# USB_INTERFACES.net
KiCad netlist of a schematic drawn in Altium Designer
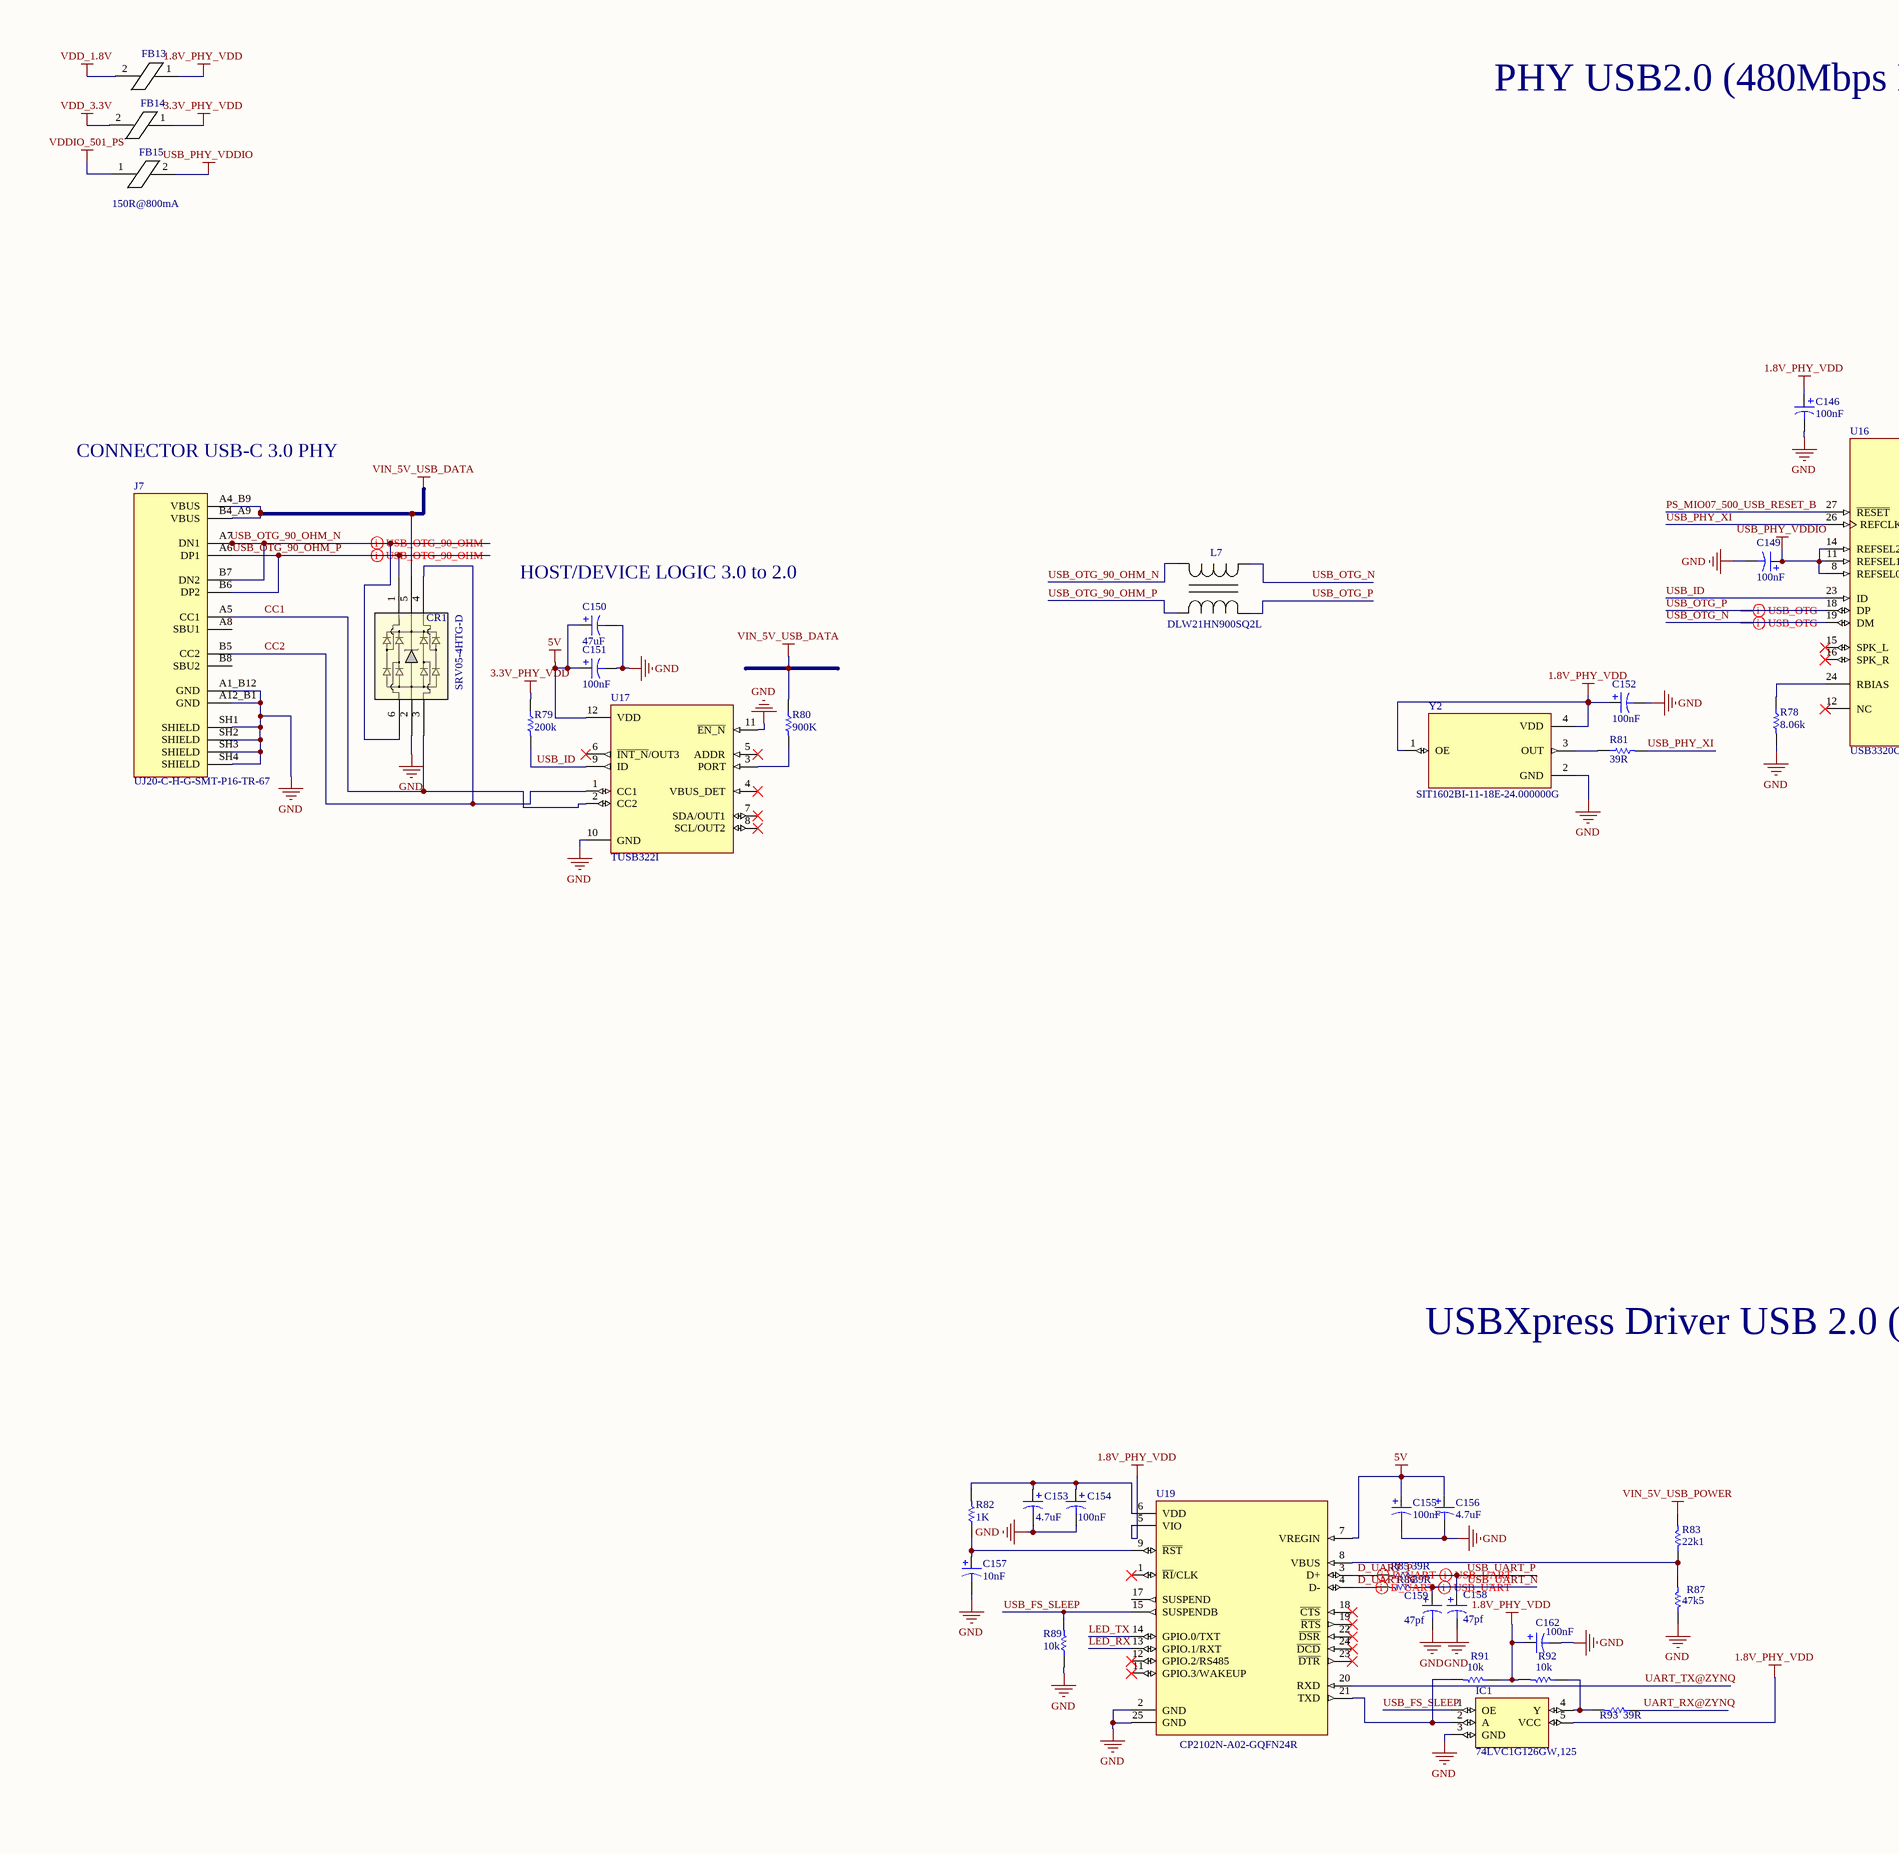
[diagram p0: USB INTERFACES.SchDoc, left]
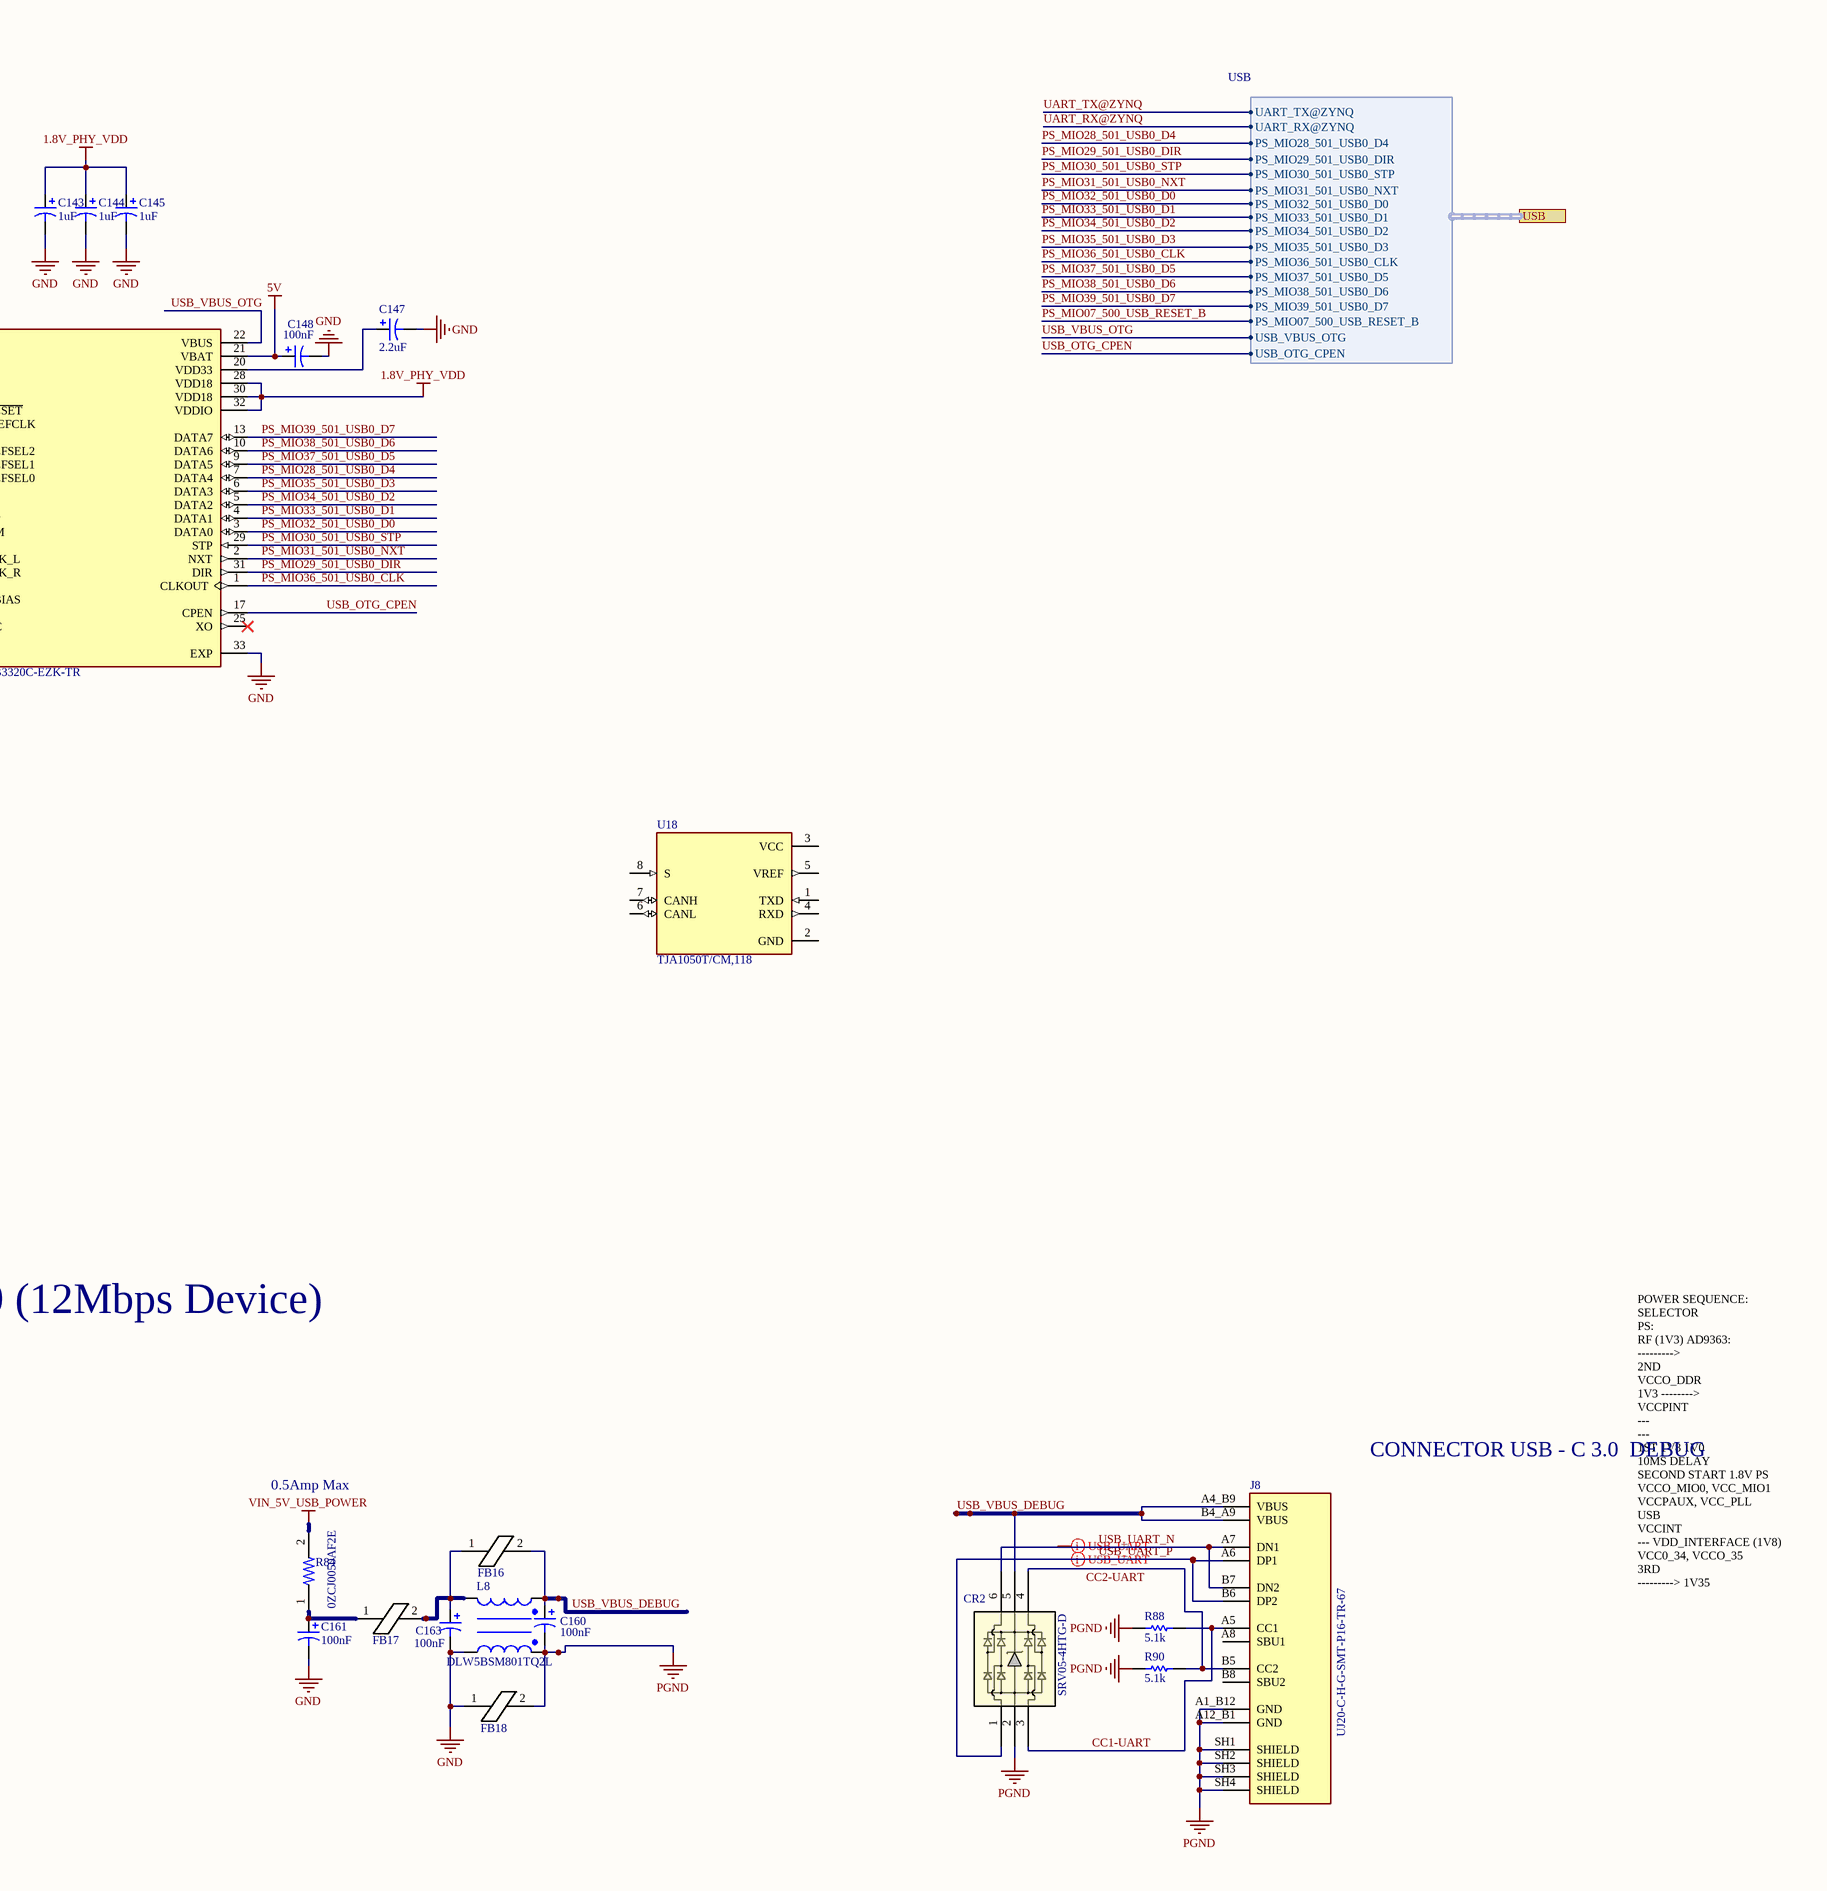
[diagram p1: USB INTERFACES.SchDoc, right]

(export (version "E")
  (design (tool "Eeschema 10.0.6"))
  (components
    (comp (ref "C143")
      (value "1uF")
      (footprint "C0805")
      (description "Polarized Capacitor (Surface Mount)")
      (fields (field (name "Comment") "Cap Pol3") (field (name "PUBLISHER") "Altium Limited"))
      (libsource (lib "") (part "Cap Pol3_1"))
    )
    (comp (ref "C144")
      (value "1uF")
      (footprint "C0805")
      (description "Polarized Capacitor (Surface Mount)")
      (fields (field (name "Comment") "Cap Pol3") (field (name "PUBLISHER") "Altium Limited"))
      (libsource (lib "") (part "Cap Pol3_1"))
    )
    (comp (ref "C145")
      (value "1uF")
      (footprint "C0805")
      (description "Polarized Capacitor (Surface Mount)")
      (fields (field (name "Comment") "Cap Pol3") (field (name "PUBLISHER") "Altium Limited"))
      (libsource (lib "") (part "Cap Pol3_1"))
    )
    (comp (ref "C146")
      (value "100nF")
      (footprint "C0805")
      (description "Polarized Capacitor (Surface Mount)")
      (fields (field (name "Comment") "Cap Pol3") (field (name "PUBLISHER") "Altium Limited"))
      (libsource (lib "") (part "Cap Pol3_1"))
    )
    (comp (ref "C147")
      (value "2.2uF")
      (footprint "C0805")
      (description "Polarized Capacitor (Surface Mount)")
      (fields (field (name "Comment") "Cap Pol3") (field (name "PUBLISHER") "Altium Limited"))
      (libsource (lib "") (part "Cap Pol3_1"))
    )
    (comp (ref "C148")
      (value "100nF")
      (footprint "C0805")
      (description "Polarized Capacitor (Surface Mount)")
      (fields (field (name "Comment") "Cap Pol3") (field (name "PUBLISHER") "Altium Limited"))
      (libsource (lib "") (part "Cap Pol3_1"))
    )
    (comp (ref "C149")
      (value "100nF")
      (footprint "C0805")
      (description "Polarized Capacitor (Surface Mount)")
      (fields (field (name "Comment") "Cap Pol3") (field (name "PUBLISHER") "Altium Limited"))
      (libsource (lib "") (part "Cap Pol3_1"))
    )
    (comp (ref "C150")
      (value "47uF")
      (footprint "C0805")
      (description "Polarized Capacitor (Surface Mount)")
      (fields (field (name "Comment") "Cap Pol3") (field (name "PUBLISHER") "Altium Limited"))
      (libsource (lib "") (part "Cap Pol3_1"))
    )
    (comp (ref "C151")
      (value "100nF")
      (footprint "C0805")
      (description "Polarized Capacitor (Surface Mount)")
      (fields (field (name "Comment") "Cap Pol3") (field (name "PUBLISHER") "Altium Limited"))
      (libsource (lib "") (part "Cap Pol3_1"))
    )
    (comp (ref "C152")
      (value "100nF")
      (footprint "C0805")
      (description "Polarized Capacitor (Surface Mount)")
      (fields (field (name "Comment") "Cap Pol3") (field (name "PUBLISHER") "Altium Limited"))
      (libsource (lib "") (part "Cap Pol3_1"))
    )
    (comp (ref "C153")
      (value "4.7uF")
      (footprint "C0805")
      (description "Polarized Capacitor (Surface Mount)")
      (fields (field (name "Comment") "Cap Pol3") (field (name "PUBLISHER") "Altium Limited"))
      (libsource (lib "") (part "Cap Pol3_1"))
    )
    (comp (ref "C154")
      (value "100nF")
      (footprint "C0805")
      (description "Polarized Capacitor (Surface Mount)")
      (fields (field (name "Comment") "Cap Pol3") (field (name "PUBLISHER") "Altium Limited"))
      (libsource (lib "") (part "Cap Pol3_1"))
    )
    (comp (ref "C155")
      (value "100nF")
      (footprint "C0805")
      (description "Polarized Capacitor (Surface Mount)")
      (fields (field (name "Comment") "Cap Pol3") (field (name "PUBLISHER") "Altium Limited"))
      (libsource (lib "Miscellaneous Devices") (part "Cap Pol3"))
    )
    (comp (ref "C156")
      (value "4.7uF")
      (footprint "C0805")
      (description "Polarized Capacitor (Surface Mount)")
      (fields (field (name "Comment") "Cap Pol3") (field (name "PUBLISHER") "Altium Limited"))
      (libsource (lib "Miscellaneous Devices") (part "Cap Pol3"))
    )
    (comp (ref "C157")
      (value "10nF")
      (footprint "C0805")
      (description "Polarized Capacitor (Surface Mount)")
      (fields (field (name "Comment") "Cap Pol3") (field (name "PUBLISHER") "Altium Limited"))
      (libsource (lib "Miscellaneous Devices") (part "Cap Pol3"))
    )
    (comp (ref "C158")
      (value "47pf")
      (footprint "C0805")
      (description "Polarized Capacitor (Surface Mount)")
      (fields (field (name "Comment") "Cap Pol3") (field (name "PUBLISHER") "Altium Limited"))
      (libsource (lib "Miscellaneous Devices") (part "Cap Pol3"))
    )
    (comp (ref "C159")
      (value "47pf")
      (footprint "C0805")
      (description "Polarized Capacitor (Surface Mount)")
      (fields (field (name "Comment") "Cap Pol3") (field (name "PUBLISHER") "Altium Limited"))
      (libsource (lib "Miscellaneous Devices") (part "Cap Pol3"))
    )
    (comp (ref "C160")
      (value "100nF")
      (footprint "C0805")
      (description "Polarized Capacitor (Surface Mount)")
      (fields (field (name "Comment") "Cap Pol3") (field (name "PUBLISHER") "Altium Limited"))
      (libsource (lib "") (part "Cap Pol3_1"))
    )
    (comp (ref "C161")
      (value "100nF")
      (footprint "C0805")
      (description "Polarized Capacitor (Surface Mount)")
      (fields (field (name "Comment") "Cap Pol3") (field (name "PUBLISHER") "Altium Limited"))
      (libsource (lib "") (part "Cap Pol3_1"))
    )
    (comp (ref "C162")
      (value "100nF")
      (footprint "C0805")
      (description "Polarized Capacitor (Surface Mount)")
      (fields (field (name "Comment") "Cap Pol3") (field (name "PUBLISHER") "Altium Limited"))
      (libsource (lib "") (part "Cap Pol3_1"))
    )
    (comp (ref "C163")
      (value "100nF")
      (footprint "C0805")
      (description "Polarized Capacitor (Surface Mount)")
      (fields (field (name "Comment") "Cap Pol3") (field (name "PUBLISHER") "Altium Limited"))
      (libsource (lib "") (part "Cap Pol3_1"))
    )
    (comp (ref "CR1")
      (value "SRV05-4HTG-D")
      (footprint "SOIC6_SOT23-6_CRA_LTF")
      (description "No Description Available")
      (libsource (lib "SRV05-4HTG-D") (part "SRV05-4HTG-D"))
    )
    (comp (ref "CR2")
      (value "SRV05-4HTG-D")
      (footprint "SOIC6_SOT23-6_CRA_LTF")
      (description "No Description Available")
      (libsource (lib "") (part "SRV05-4HTG-D_1"))
    )
    (comp (ref "FB13")
      (value "FERRITA")
      (footprint "0805R")
      (libsource (lib "lib_protel_HC") (part "FERRITA"))
    )
    (comp (ref "FB14")
      (value "FERRITA")
      (footprint "0805R")
      (libsource (lib "lib_protel_HC") (part "FERRITA"))
    )
    (comp (ref "FB15")
      (value "FERRITA")
      (footprint "0805R")
      (libsource (lib "lib_protel_HC") (part "FERRITA"))
    )
    (comp (ref "FB16")
      (value "FERRITA")
      (footprint "0805R")
      (libsource (lib "lib_protel_HC") (part "FERRITA"))
    )
    (comp (ref "FB17")
      (value "FERRITA")
      (footprint "0805R")
      (libsource (lib "lib_protel_HC") (part "FERRITA"))
    )
    (comp (ref "FB18")
      (value "FERRITA")
      (footprint "0805R")
      (libsource (lib "lib_protel_HC") (part "FERRITA"))
    )
    (comp (ref "IC1")
      (value "74LVC1G126GW,125")
      (footprint "SOT65P212X110-5N")
      (description "Buffer, Non-Inverting 1 Element 1 Bit per Element 3-State Output 5-TSSOP")
      (fields (field (name "MF") "Nexperia USA Inc."))
      (libsource (lib "74LVC1G126GW_125") (part "74LVC1G126GW,125"))
    )
    (comp (ref "J7")
      (value "UJ20-C-H-G-SMT-P16-TR-67")
      (footprint "SAMESKY_UJ20-C-H-G-SMT-P16-TR-67")
      (libsource (lib "") (part "UJ20-C-H-G-SMT-P16-TR-67_1"))
    )
    (comp (ref "J8")
      (value "UJ20-C-H-G-SMT-P16-TR-67")
      (footprint "SAMESKY_UJ20-C-H-G-SMT-P16-TR-67")
      (libsource (lib "UJ20-C-H-G-SMT-P16-TR-67") (part "UJ20-C-H-G-SMT-P16-TR-67"))
    )
    (comp (ref "L7")
      (value "DLW21HN900SQ2L")
      (footprint "IND_DLW21H_0805_MUR")
      (description "No Description Available")
      (libsource (lib "DLW21HN900SQ2L") (part "DLW21HN900SQ2L"))
    )
    (comp (ref "L8")
      (value "DLW5BSM801TQ2L")
      (footprint "FIL_DLW5BSM801TQ2L")
      (description "2 Line Common Mode Choke Surface Mount 800 Ohms @ 100MHz 2A DCR 56mOhm")
      (fields (field (name "MF") "Murata") (field (name "DIGI-KEY_PART_NUMBER") "490-9569-1-ND"))
      (libsource (lib "DLW5BSM801TQ2L") (part "DLW5BSM801TQ2L"))
    )
    (comp (ref "R78")
      (value "8.06k")
      (footprint "0603")
      (description "Resistor")
      (fields
        (field (name "MANUFACTURER") "Generic Components")
        (field (name "Comment") "Res1")
        (field (name "PUBLISHER") "Altium Limited")
      )
      (libsource (lib "lib_protel_HC") (part "Res1_1"))
    )
    (comp (ref "R79")
      (value "200k")
      (footprint "0603")
      (description "Resistor")
      (fields
        (field (name "MANUFACTURER") "Generic Components")
        (field (name "Comment") "Res1")
        (field (name "PUBLISHER") "Altium Limited")
      )
      (libsource (lib "lib_protel_HC") (part "Res1_1"))
    )
    (comp (ref "R80")
      (value "900K")
      (footprint "0603")
      (description "Resistor")
      (fields
        (field (name "MANUFACTURER") "Generic Components")
        (field (name "Comment") "Res1")
        (field (name "PUBLISHER") "Altium Limited")
      )
      (libsource (lib "lib_protel_HC") (part "Res1_1"))
    )
    (comp (ref "R81")
      (value "39R")
      (footprint "0603")
      (description "Resistor")
      (fields
        (field (name "MANUFACTURER") "Generic Components")
        (field (name "Comment") "Res1")
        (field (name "PUBLISHER") "Altium Limited")
      )
      (libsource (lib "lib_protel_HC") (part "Res1_1"))
    )
    (comp (ref "R82")
      (value "1K")
      (footprint "0603")
      (description "Resistor")
      (fields
        (field (name "MANUFACTURER") "Generic Components")
        (field (name "Comment") "Res1")
        (field (name "PUBLISHER") "Altium Limited")
      )
      (libsource (lib "lib_protel_HC") (part "Res1_1"))
    )
    (comp (ref "R83")
      (value "22k1")
      (footprint "0603")
      (description "Resistor")
      (fields
        (field (name "MANUFACTURER") "Generic Components")
        (field (name "Comment") "Res1")
        (field (name "PUBLISHER") "Altium Limited")
      )
      (libsource (lib "lib_protel_HC") (part "Res1_1"))
    )
    (comp (ref "R84")
      (value "0ZCJ0050AF2E")
      (footprint "RESC3216X125N")
      (description "1206 SMT PPTC ¦ 0.50 Ih ¦ 24V")
      (fields (field (name "MF") "Bel Fuse"))
      (libsource (lib "0ZCJ0050AF2E") (part "0ZCJ0050AF2E"))
    )
    (comp (ref "R85")
      (value "39R")
      (footprint "0603")
      (description "Resistor")
      (fields
        (field (name "MANUFACTURER") "Generic Components")
        (field (name "Comment") "Res1")
        (field (name "PUBLISHER") "Altium Limited")
      )
      (libsource (lib "lib_protel_HC") (part "Res1_1"))
    )
    (comp (ref "R86")
      (value "39R")
      (footprint "0603")
      (description "Resistor")
      (fields
        (field (name "MANUFACTURER") "Generic Components")
        (field (name "Comment") "Res1")
        (field (name "PUBLISHER") "Altium Limited")
      )
      (libsource (lib "lib_protel_HC") (part "Res1_1"))
    )
    (comp (ref "R87")
      (value "47k5")
      (footprint "0603")
      (description "Resistor")
      (fields
        (field (name "MANUFACTURER") "Generic Components")
        (field (name "Comment") "Res1")
        (field (name "PUBLISHER") "Altium Limited")
      )
      (libsource (lib "lib_protel_HC") (part "Res1_1"))
    )
    (comp (ref "R88")
      (value "5.1k")
      (footprint "0603")
      (description "Resistor")
      (fields
        (field (name "MANUFACTURER") "Generic Components")
        (field (name "Comment") "Res1")
        (field (name "PUBLISHER") "Altium Limited")
      )
      (libsource (lib "lib_protel_HC") (part "Res1_1"))
    )
    (comp (ref "R89")
      (value "10k")
      (footprint "0603")
      (description "Resistor")
      (fields
        (field (name "MANUFACTURER") "Generic Components")
        (field (name "Comment") "Res1")
        (field (name "PUBLISHER") "Altium Limited")
      )
      (libsource (lib "lib_protel_HC") (part "Res1_1"))
    )
    (comp (ref "R90")
      (value "5.1k")
      (footprint "0603")
      (description "Resistor")
      (fields
        (field (name "MANUFACTURER") "Generic Components")
        (field (name "Comment") "Res1")
        (field (name "PUBLISHER") "Altium Limited")
      )
      (libsource (lib "lib_protel_HC") (part "Res1_1"))
    )
    (comp (ref "R91")
      (value "10k")
      (footprint "0603")
      (description "Resistor")
      (fields
        (field (name "MANUFACTURER") "Generic Components")
        (field (name "Comment") "Res1")
        (field (name "PUBLISHER") "Altium Limited")
      )
      (libsource (lib "lib_protel_HC") (part "Res1_1"))
    )
    (comp (ref "R92")
      (value "10k")
      (footprint "0603")
      (description "Resistor")
      (fields
        (field (name "MANUFACTURER") "Generic Components")
        (field (name "Comment") "Res1")
        (field (name "PUBLISHER") "Altium Limited")
      )
      (libsource (lib "lib_protel_HC") (part "Res1_1"))
    )
    (comp (ref "R93")
      (value "39R")
      (footprint "0603")
      (description "Resistor")
      (fields
        (field (name "MANUFACTURER") "Generic Components")
        (field (name "Comment") "Res1")
        (field (name "PUBLISHER") "Altium Limited")
      )
      (libsource (lib "lib_protel_HC") (part "Res1_1"))
    )
    (comp (ref "U16")
      (value "USB3320C-EZK-TR")
      (footprint "QFN50P500X500X100-33N")
      (fields (field (name "MF") "Microchip"))
      (libsource (lib "USB3320C-EZK-TR") (part "USB3320C-EZK-TR"))
    )
    (comp (ref "U17")
      (value "TUSB322I")
      (footprint "IC_TUSB320IRWBR")
      (description "USB Type-C configuration channel logic and port control")
      (fields (field (name "MF") "Texas Instruments") (field (name "MP") "TUSB320IRWBR"))
      (libsource (lib "TUSB320IRWBR") (part "TUSB320IRWBR"))
    )
    (comp (ref "U18")
      (value "TJA1050T/CM,118")
      (footprint "SOIC127P600X175-8N")
      (description "1/1 Transceiver Half CANbus 8-SO")
      (fields (field (name "MF") "NXP USA"))
      (libsource (lib "TJA1050T_CM_118") (part "TJA1050T/CM,118"))
    )
    (comp (ref "U19")
      (value "CP2102N-A02-GQFN24R")
      (footprint "QFN50P400X400X80-25N")
      (libsource (lib "CP2102N-A02-GQFN24R") (part "CP2102N-A02-GQFN24R"))
    )
    (comp (ref "Y2")
      (value "SIT1602BI-11-18E-24.000000G")
      (footprint "OSC_SIT1602BI-11-18E-24.000000G")
      (description "Oscillator MEMS 24MHz Â±20ppm (Stability) 15pF HCMOS/LVCMOS 55% 1.8V 4-Pin PQFN SMD T/R")
      (fields (field (name "MF") "SiTime"))
      (libsource (lib "SIT1602BI-11-18E-24.000000G") (part "SIT1602BI-11-18E-24.000000G"))
    )
  )
  (nets
    (net (code "2") (name "/CC1") (class "Default")
      (node (ref "CR1") (pin "3") (pinfunction "3_3") (pintype "passive"))
      (node (ref "J7") (pin "A5") (pinfunction "CC1_A5") (pintype "passive"))
      (node (ref "U17") (pin "2") (pinfunction "CC2_2") (pintype "bidirectional"))
    )
    (net (code "3") (name "/CC1-UART") (class "Default")
      (node (ref "CR2") (pin "3") (pinfunction "3_3") (pintype "passive"))
      (node (ref "J8") (pin "A5") (pinfunction "CC1_A5") (pintype "passive"))
      (node (ref "R88") (pin "2") (pinfunction "2_2") (pintype "passive"))
    )
    (net (code "4") (name "/CC2") (class "Default")
      (node (ref "CR1") (pin "4") (pinfunction "4_4") (pintype "passive"))
      (node (ref "J7") (pin "B5") (pinfunction "CC2_B5") (pintype "passive"))
      (node (ref "U17") (pin "1") (pinfunction "CC1_1") (pintype "bidirectional"))
    )
    (net (code "5") (name "/CC2-UART") (class "Default")
      (node (ref "CR2") (pin "4") (pinfunction "4_4") (pintype "passive"))
      (node (ref "J8") (pin "B5") (pinfunction "CC2_B5") (pintype "passive"))
      (node (ref "R90") (pin "2") (pinfunction "2_2") (pintype "passive"))
    )
    (net (code "6") (name "/D_UART_N") (class "Default")
      (node (ref "R86") (pin "2") (pinfunction "2_2") (pintype "passive"))
      (node (ref "U19") (pin "4") (pinfunction "D-_4") (pintype "bidirectional"))
    )
    (net (code "7") (name "/D_UART_P") (class "Default")
      (node (ref "R85") (pin "2") (pinfunction "2_2") (pintype "passive"))
      (node (ref "U19") (pin "3") (pinfunction "D+_3") (pintype "bidirectional"))
    )
    (net (code "8") (name "/LED_RX") (class "Default")
      (node (ref "U19") (pin "13") (pinfunction "GPIO.1/RXT_13") (pintype "bidirectional"))
    )
    (net (code "9") (name "/LED_TX") (class "Default")
      (node (ref "U19") (pin "14") (pinfunction "GPIO.0/TXT_14") (pintype "bidirectional"))
    )
    (net (code "10") (name "/PS_MIO07_500_USB_RESET_B") (class "Default")
      (node (ref "U16") (pin "27") (pinfunction "~{RESET}_27") (pintype "input"))
    )
    (net (code "11") (name "/PS_MIO28_501_USB0_D4") (class "Default")
      (node (ref "U16") (pin "7") (pinfunction "DATA4_7") (pintype "bidirectional"))
    )
    (net (code "12") (name "/PS_MIO29_501_USB0_DIR") (class "Default")
      (node (ref "U16") (pin "31") (pinfunction "DIR_31") (pintype "output"))
    )
    (net (code "13") (name "/PS_MIO30_501_USB0_STP") (class "Default")
      (node (ref "U16") (pin "29") (pinfunction "STP_29") (pintype "input"))
    )
    (net (code "14") (name "/PS_MIO31_501_USB0_NXT") (class "Default")
      (node (ref "U16") (pin "2") (pinfunction "NXT_2") (pintype "output"))
    )
    (net (code "15") (name "/PS_MIO32_501_USB0_D0") (class "Default")
      (node (ref "U16") (pin "3") (pinfunction "DATA0_3") (pintype "bidirectional"))
    )
    (net (code "16") (name "/PS_MIO33_501_USB0_D1") (class "Default")
      (node (ref "U16") (pin "4") (pinfunction "DATA1_4") (pintype "bidirectional"))
    )
    (net (code "17") (name "/PS_MIO34_501_USB0_D2") (class "Default")
      (node (ref "U16") (pin "5") (pinfunction "DATA2_5") (pintype "bidirectional"))
    )
    (net (code "18") (name "/PS_MIO35_501_USB0_D3") (class "Default")
      (node (ref "U16") (pin "6") (pinfunction "DATA3_6") (pintype "bidirectional"))
    )
    (net (code "19") (name "/PS_MIO36_501_USB0_CLK") (class "Default")
      (node (ref "U16") (pin "1") (pinfunction "CLKOUT_1") (pintype "output"))
    )
    (net (code "20") (name "/PS_MIO37_501_USB0_D5") (class "Default")
      (node (ref "U16") (pin "9") (pinfunction "DATA5_9") (pintype "bidirectional"))
    )
    (net (code "21") (name "/PS_MIO38_501_USB0_D6") (class "Default")
      (node (ref "U16") (pin "10") (pinfunction "DATA6_10") (pintype "bidirectional"))
    )
    (net (code "22") (name "/PS_MIO39_501_USB0_D7") (class "Default")
      (node (ref "U16") (pin "13") (pinfunction "DATA7_13") (pintype "bidirectional"))
    )
    (net (code "23") (name "/UART_RX@ZYNQ") (class "Default")
      (node (ref "R93") (pin "1") (pinfunction "1_1") (pintype "passive"))
    )
    (net (code "24") (name "/UART_TX@ZYNQ") (class "Default")
      (node (ref "U19") (pin "20") (pinfunction "RXD_20") (pintype "input"))
    )
    (net (code "25") (name "/USB_FS_SLEEP") (class "Default")
      (node (ref "IC1") (pin "1") (pinfunction "OE_1") (pintype "bidirectional"))
      (node (ref "R89") (pin "2") (pinfunction "2_2") (pintype "passive"))
      (node (ref "U19") (pin "15") (pinfunction "SUSPENDB_15") (pintype "output"))
    )
    (net (code "26") (name "/USB_ID") (class "Default")
      (node (ref "R79") (pin "2") (pinfunction "2_2") (pintype "passive"))
      (node (ref "U16") (pin "23") (pinfunction "ID_23") (pintype "input"))
      (node (ref "U17") (pin "9") (pinfunction "ID_9") (pintype "output"))
    )
    (net (code "27") (name "/USB_OTG_90_OHM_N") (class "Default")
      (node (ref "CR1") (pin "6") (pinfunction "6_6") (pintype "passive"))
      (node (ref "J7") (pin "A7") (pinfunction "DN1_A7") (pintype "passive"))
      (node (ref "J7") (pin "B7") (pinfunction "DN2_B7") (pintype "passive"))
      (node (ref "L7") (pin "1") (pinfunction "1_1") (pintype "passive"))
    )
    (net (code "28") (name "/USB_OTG_90_OHM_P") (class "Default")
      (node (ref "CR1") (pin "1") (pinfunction "1_1") (pintype "passive"))
      (node (ref "J7") (pin "A6") (pinfunction "DP1_A6") (pintype "passive"))
      (node (ref "J7") (pin "B6") (pinfunction "DP2_B6") (pintype "passive"))
      (node (ref "L7") (pin "4") (pinfunction "4_4") (pintype "passive"))
    )
    (net (code "29") (name "/USB_OTG_CPEN") (class "Default")
      (node (ref "U16") (pin "17") (pinfunction "CPEN_17") (pintype "output"))
    )
    (net (code "30") (name "/USB_OTG_N") (class "Default")
      (node (ref "L7") (pin "2") (pinfunction "2_2") (pintype "passive"))
      (node (ref "U16") (pin "19") (pinfunction "DM_19") (pintype "bidirectional"))
    )
    (net (code "31") (name "/USB_OTG_P") (class "Default")
      (node (ref "L7") (pin "3") (pinfunction "3_3") (pintype "passive"))
      (node (ref "U16") (pin "18") (pinfunction "DP_18") (pintype "bidirectional"))
    )
    (net (code "32") (name "/USB_PHY_XI") (class "Default")
      (node (ref "R81") (pin "2") (pinfunction "2_2") (pintype "passive"))
      (node (ref "U16") (pin "26") (pinfunction "REFCLK_26") (pintype "input"))
    )
    (net (code "33") (name "/USB_UART_N") (class "Default")
      (node (ref "C159") (pin "1") (pinfunction "1_1") (pintype "passive"))
      (node (ref "CR2") (pin "6") (pinfunction "6_6") (pintype "passive"))
      (node (ref "J8") (pin "A7") (pinfunction "DN1_A7") (pintype "passive"))
      (node (ref "J8") (pin "B7") (pinfunction "DN2_B7") (pintype "passive"))
      (node (ref "R86") (pin "1") (pinfunction "1_1") (pintype "passive"))
    )
    (net (code "34") (name "/USB_UART_P") (class "Default")
      (node (ref "C158") (pin "1") (pinfunction "1_1") (pintype "passive"))
      (node (ref "CR2") (pin "1") (pinfunction "1_1") (pintype "passive"))
      (node (ref "J8") (pin "A6") (pinfunction "DP1_A6") (pintype "passive"))
      (node (ref "J8") (pin "B6") (pinfunction "DP2_B6") (pintype "passive"))
      (node (ref "R85") (pin "1") (pinfunction "1_1") (pintype "passive"))
    )
    (net (code "35") (name "/USB_VBUS_DEBUG") (class "Default")
      (node (ref "C160") (pin "1") (pinfunction "1_1") (pintype "passive"))
      (node (ref "CR2") (pin "5") (pinfunction "5_5") (pintype "passive"))
      (node (ref "FB16") (pin "2") (pintype "passive"))
      (node (ref "J8") (pin "A4_B9") (pinfunction "VBUS_A4_B9") (pintype "passive"))
      (node (ref "J8") (pin "B4_A9") (pinfunction "VBUS_B4_A9") (pintype "passive"))
      (node (ref "L8") (pin "1") (pinfunction "1_1") (pintype "passive"))
    )
    (net (code "36") (name "/USB_VBUS_OTG") (class "Default")
      (node (ref "U16") (pin "22") (pinfunction "VBUS_22") (pintype "power_in"))
    )
    (net (code "38") (name "1.8V_PHY_VDD") (class "Default")
      (node (ref "C143") (pin "1") (pinfunction "1_1") (pintype "passive"))
      (node (ref "C144") (pin "1") (pinfunction "1_1") (pintype "passive"))
      (node (ref "C145") (pin "1") (pinfunction "1_1") (pintype "passive"))
      (node (ref "C146") (pin "1") (pinfunction "1_1") (pintype "passive"))
      (node (ref "C152") (pin "1") (pinfunction "1_1") (pintype "passive"))
      (node (ref "C162") (pin "1") (pinfunction "1_1") (pintype "passive"))
      (node (ref "FB13") (pin "1") (pintype "passive"))
      (node (ref "IC1") (pin "5") (pinfunction "VCC_5") (pintype "bidirectional"))
      (node (ref "R91") (pin "1") (pinfunction "1_1") (pintype "passive"))
      (node (ref "R92") (pin "2") (pinfunction "2_2") (pintype "passive"))
      (node (ref "U16") (pin "28") (pinfunction "VDD18_28") (pintype "power_in"))
      (node (ref "U16") (pin "30") (pinfunction "VDD18_30") (pintype "power_in"))
      (node (ref "U16") (pin "32") (pinfunction "VDDIO_32") (pintype "power_in"))
      (node (ref "U19") (pin "5") (pinfunction "VIO_5") (pintype "power_in"))
      (node (ref "Y2") (pin "1") (pinfunction "OE_1") (pintype "bidirectional"))
      (node (ref "Y2") (pin "4") (pinfunction "VDD_4") (pintype "power_in"))
    )
    (net (code "39") (name "3.3V_PHY_VDD") (class "Default")
      (node (ref "FB14") (pin "1") (pintype "passive"))
      (node (ref "R79") (pin "1") (pinfunction "1_1") (pintype "passive"))
    )
    (net (code "40") (name "5V") (class "Default")
      (node (ref "C148") (pin "1") (pinfunction "1_1") (pintype "passive"))
      (node (ref "C150") (pin "1") (pinfunction "1_1") (pintype "passive"))
      (node (ref "C151") (pin "1") (pinfunction "1_1") (pintype "passive"))
      (node (ref "C155") (pin "1") (pinfunction "1_1") (pintype "passive"))
      (node (ref "C156") (pin "1") (pinfunction "1_1") (pintype "passive"))
      (node (ref "U16") (pin "21") (pinfunction "VBAT_21") (pintype "power_in"))
      (node (ref "U17") (pin "12") (pinfunction "VDD_12") (pintype "power_in"))
      (node (ref "U19") (pin "7") (pinfunction "VREGIN_7") (pintype "input"))
    )
    (net (code "41") (name "GND") (class "Default")
      (node (ref "C143") (pin "2") (pinfunction "2_2") (pintype "passive"))
      (node (ref "C144") (pin "2") (pinfunction "2_2") (pintype "passive"))
      (node (ref "C145") (pin "2") (pinfunction "2_2") (pintype "passive"))
      (node (ref "C146") (pin "2") (pinfunction "2_2") (pintype "passive"))
      (node (ref "C147") (pin "2") (pinfunction "2_2") (pintype "passive"))
      (node (ref "C148") (pin "2") (pinfunction "2_2") (pintype "passive"))
      (node (ref "C149") (pin "2") (pinfunction "2_2") (pintype "passive"))
      (node (ref "C150") (pin "2") (pinfunction "2_2") (pintype "passive"))
      (node (ref "C151") (pin "2") (pinfunction "2_2") (pintype "passive"))
      (node (ref "C152") (pin "2") (pinfunction "2_2") (pintype "passive"))
      (node (ref "C153") (pin "2") (pinfunction "2_2") (pintype "passive"))
      (node (ref "C154") (pin "2") (pinfunction "2_2") (pintype "passive"))
      (node (ref "C155") (pin "2") (pinfunction "2_2") (pintype "passive"))
      (node (ref "C156") (pin "2") (pinfunction "2_2") (pintype "passive"))
      (node (ref "C157") (pin "2") (pinfunction "2_2") (pintype "passive"))
      (node (ref "C158") (pin "2") (pinfunction "2_2") (pintype "passive"))
      (node (ref "C159") (pin "2") (pinfunction "2_2") (pintype "passive"))
      (node (ref "C161") (pin "2") (pinfunction "2_2") (pintype "passive"))
      (node (ref "C162") (pin "2") (pinfunction "2_2") (pintype "passive"))
      (node (ref "C163") (pin "2") (pinfunction "2_2") (pintype "passive"))
      (node (ref "CR1") (pin "2") (pinfunction "2_2") (pintype "passive"))
      (node (ref "FB18") (pin "1") (pintype "passive"))
      (node (ref "IC1") (pin "3") (pinfunction "GND_3") (pintype "bidirectional"))
      (node (ref "J7") (pin "A12_B1") (pinfunction "GND_A12_B1") (pintype "passive"))
      (node (ref "J7") (pin "A1_B12") (pinfunction "GND_A1_B12") (pintype "passive"))
      (node (ref "J7") (pin "SH1") (pinfunction "SHIELD_SH1") (pintype "passive"))
      (node (ref "J7") (pin "SH2") (pinfunction "SHIELD_SH2") (pintype "passive"))
      (node (ref "J7") (pin "SH3") (pinfunction "SHIELD_SH3") (pintype "passive"))
      (node (ref "J7") (pin "SH4") (pinfunction "SHIELD_SH4") (pintype "passive"))
      (node (ref "L8") (pin "3") (pinfunction "3_3") (pintype "passive"))
      (node (ref "R78") (pin "2") (pinfunction "2_2") (pintype "passive"))
      (node (ref "R87") (pin "1") (pinfunction "1_1") (pintype "passive"))
      (node (ref "R89") (pin "1") (pinfunction "1_1") (pintype "passive"))
      (node (ref "U16") (pin "33") (pinfunction "EXP_33") (pintype "power_in"))
      (node (ref "U17") (pin "10") (pinfunction "GND_10") (pintype "power_in"))
      (node (ref "U17") (pin "11") (pinfunction "~{EN_N}_11") (pintype "input"))
      (node (ref "U19") (pin "2") (pinfunction "GND_2") (pintype "power_in"))
      (node (ref "U19") (pin "25") (pinfunction "GND_25") (pintype "power_in"))
      (node (ref "Y2") (pin "2") (pinfunction "GND_2") (pintype "power_in"))
    )
    (net (code "42") (name "Net-(C161-Pad1)") (class "Default")
      (node (ref "C161") (pin "1") (pinfunction "1_1") (pintype "passive"))
      (node (ref "FB17") (pin "1") (pintype "passive"))
      (node (ref "R84") (pin "1") (pinfunction "1_1") (pintype "passive"))
    )
    (net (code "43") (name "Net-(C163-Pad1)") (class "Default")
      (node (ref "C163") (pin "1") (pinfunction "1_1") (pintype "passive"))
      (node (ref "FB16") (pin "1") (pintype "passive"))
      (node (ref "FB17") (pin "2") (pintype "passive"))
      (node (ref "L8") (pin "2") (pinfunction "2_2") (pintype "passive"))
    )
    (net (code "44") (name "Net-(IC1-A)") (class "Default")
      (node (ref "IC1") (pin "2") (pinfunction "A_2") (pintype "bidirectional"))
      (node (ref "R91") (pin "2") (pinfunction "2_2") (pintype "passive"))
      (node (ref "U19") (pin "21") (pinfunction "TXD_21") (pintype "output"))
    )
    (net (code "45") (name "Net-(IC1-Y)") (class "Default")
      (node (ref "IC1") (pin "4") (pinfunction "Y_4") (pintype "bidirectional"))
      (node (ref "R92") (pin "1") (pinfunction "1_1") (pintype "passive"))
      (node (ref "R93") (pin "2") (pinfunction "2_2") (pintype "passive"))
    )
    (net (code "46") (name "Net-(U16-RBIAS)") (class "Default")
      (node (ref "R78") (pin "1") (pinfunction "1_1") (pintype "passive"))
      (node (ref "U16") (pin "24") (pinfunction "RBIAS_24") (pintype "passive"))
    )
    (net (code "47") (name "Net-(U16-VDD33)") (class "Default")
      (node (ref "C147") (pin "1") (pinfunction "1_1") (pintype "passive"))
      (node (ref "U16") (pin "20") (pinfunction "VDD33_20") (pintype "power_in"))
    )
    (net (code "48") (name "Net-(U17-PORT)") (class "Default")
      (node (ref "R80") (pin "2") (pinfunction "2_2") (pintype "passive"))
      (node (ref "U17") (pin "3") (pinfunction "PORT_3") (pintype "input"))
    )
    (net (code "49") (name "Net-(U19-VBUS)") (class "Default")
      (node (ref "R83") (pin "1") (pinfunction "1_1") (pintype "passive"))
      (node (ref "R87") (pin "2") (pinfunction "2_2") (pintype "passive"))
      (node (ref "U19") (pin "8") (pinfunction "VBUS_8") (pintype "input"))
    )
    (net (code "50") (name "Net-(U19-VDD)") (class "Default")
      (node (ref "C153") (pin "1") (pinfunction "1_1") (pintype "passive"))
      (node (ref "C154") (pin "1") (pinfunction "1_1") (pintype "passive"))
      (node (ref "R82") (pin "2") (pinfunction "2_2") (pintype "passive"))
      (node (ref "U19") (pin "6") (pinfunction "VDD_6") (pintype "power_in"))
    )
    (net (code "51") (name "Net-(U19-~{RST})") (class "Default")
      (node (ref "C157") (pin "1") (pinfunction "1_1") (pintype "passive"))
      (node (ref "R82") (pin "1") (pinfunction "1_1") (pintype "passive"))
      (node (ref "U19") (pin "9") (pinfunction "~{RST}_9") (pintype "bidirectional"))
    )
    (net (code "52") (name "Net-(Y2-OUT)") (class "Default")
      (node (ref "R81") (pin "1") (pinfunction "1_1") (pintype "passive"))
      (node (ref "Y2") (pin "3") (pinfunction "OUT_3") (pintype "output"))
    )
    (net (code "53") (name "PGND") (class "Default")
      (node (ref "C160") (pin "2") (pinfunction "2_2") (pintype "passive"))
      (node (ref "CR2") (pin "2") (pinfunction "2_2") (pintype "passive"))
      (node (ref "FB18") (pin "2") (pintype "passive"))
      (node (ref "J8") (pin "A12_B1") (pinfunction "GND_A12_B1") (pintype "passive"))
      (node (ref "J8") (pin "A1_B12") (pinfunction "GND_A1_B12") (pintype "passive"))
      (node (ref "J8") (pin "SH1") (pinfunction "SHIELD_SH1") (pintype "passive"))
      (node (ref "J8") (pin "SH2") (pinfunction "SHIELD_SH2") (pintype "passive"))
      (node (ref "J8") (pin "SH3") (pinfunction "SHIELD_SH3") (pintype "passive"))
      (node (ref "J8") (pin "SH4") (pinfunction "SHIELD_SH4") (pintype "passive"))
      (node (ref "L8") (pin "4") (pinfunction "4_4") (pintype "passive"))
      (node (ref "R88") (pin "1") (pinfunction "1_1") (pintype "passive"))
      (node (ref "R90") (pin "1") (pinfunction "1_1") (pintype "passive"))
    )
    (net (code "54") (name "USB_PHY_VDDIO") (class "Default")
      (node (ref "C149") (pin "1") (pinfunction "1_1") (pintype "passive"))
      (node (ref "FB15") (pin "2") (pintype "passive"))
      (node (ref "U16") (pin "11") (pinfunction "REFSEL1_11") (pintype "input"))
      (node (ref "U16") (pin "14") (pinfunction "REFSEL2_14") (pintype "input"))
      (node (ref "U16") (pin "8") (pinfunction "REFSEL0_8") (pintype "input"))
    )
    (net (code "55") (name "VDDIO_501_PS") (class "Default")
      (node (ref "FB15") (pin "1") (pintype "passive"))
    )
    (net (code "56") (name "VDD_1.8V") (class "Default") (node (ref "FB13") (pin "2") (pintype "passive")))
    (net (code "57") (name "VDD_3.3V") (class "Default") (node (ref "FB14") (pin "2") (pintype "passive")))
    (net (code "58") (name "VIN_5V_USB_DATA") (class "Default")
      (node (ref "CR1") (pin "5") (pinfunction "5_5") (pintype "passive"))
      (node (ref "J7") (pin "A4_B9") (pinfunction "VBUS_A4_B9") (pintype "passive"))
      (node (ref "J7") (pin "B4_A9") (pinfunction "VBUS_B4_A9") (pintype "passive"))
      (node (ref "R80") (pin "1") (pinfunction "1_1") (pintype "passive"))
    )
    (net (code "59") (name "VIN_5V_USB_POWER") (class "Default")
      (node (ref "R83") (pin "2") (pinfunction "2_2") (pintype "passive"))
      (node (ref "R84") (pin "2") (pinfunction "2_2") (pintype "passive"))
    )
    (net (code "60") (name "unconnected-(J7-SBU1-PadA8)") (class "Default")
      (node (ref "J7") (pin "A8") (pinfunction "SBU1_A8") (pintype "passive"))
    )
    (net (code "61") (name "unconnected-(J7-SBU2-PadB8)") (class "Default")
      (node (ref "J7") (pin "B8") (pinfunction "SBU2_B8") (pintype "passive"))
    )
    (net (code "62") (name "unconnected-(J8-SBU1-PadA8)") (class "Default")
      (node (ref "J8") (pin "A8") (pinfunction "SBU1_A8") (pintype "passive"))
    )
    (net (code "63") (name "unconnected-(J8-SBU2-PadB8)") (class "Default")
      (node (ref "J8") (pin "B8") (pinfunction "SBU2_B8") (pintype "passive"))
    )
    (net (code "64") (name "unconnected-(U16-NC-Pad12)") (class "Default")
      (node (ref "U16") (pin "12") (pinfunction "NC_12") (pintype "passive+no_connect"))
    )
    (net (code "65") (name "unconnected-(U16-SPK_L-Pad15)") (class "Default")
      (node (ref "U16") (pin "15") (pinfunction "SPK_L_15") (pintype "bidirectional+no_connect"))
    )
    (net (code "66") (name "unconnected-(U16-SPK_R-Pad16)") (class "Default")
      (node (ref "U16") (pin "16") (pinfunction "SPK_R_16") (pintype "bidirectional+no_connect"))
    )
    (net (code "67") (name "unconnected-(U16-XO-Pad25)") (class "Default")
      (node (ref "U16") (pin "25") (pinfunction "XO_25") (pintype "output+no_connect"))
    )
    (net (code "68") (name "unconnected-(U17-ADDR-Pad5)") (class "Default")
      (node (ref "U17") (pin "5") (pinfunction "ADDR_5") (pintype "input+no_connect"))
    )
    (net (code "69") (name "unconnected-(U17-SCL{slash}OUT2-Pad8)") (class "Default")
      (node (ref "U17") (pin "8") (pinfunction "SCL/OUT2_8") (pintype "bidirectional+no_connect"))
    )
    (net (code "70") (name "unconnected-(U17-SDA{slash}OUT1-Pad7)") (class "Default")
      (node (ref "U17") (pin "7") (pinfunction "SDA/OUT1_7") (pintype "bidirectional+no_connect"))
    )
    (net (code "71") (name "unconnected-(U17-VBUS_DET-Pad4)") (class "Default")
      (node (ref "U17") (pin "4") (pinfunction "VBUS_DET_4") (pintype "input+no_connect"))
    )
    (net (code "72") (name "unconnected-(U17-~{INT_N}{slash}OUT3-Pad6)") (class "Default")
      (node (ref "U17") (pin "6") (pinfunction "~{INT_N}/OUT3_6") (pintype "output+no_connect"))
    )
    (net (code "73") (name "unconnected-(U18-CANH-Pad7)") (class "Default")
      (node (ref "U18") (pin "7") (pinfunction "CANH_7") (pintype "bidirectional"))
    )
    (net (code "74") (name "unconnected-(U18-CANL-Pad6)") (class "Default")
      (node (ref "U18") (pin "6") (pinfunction "CANL_6") (pintype "bidirectional"))
    )
    (net (code "75") (name "unconnected-(U18-GND-Pad2)") (class "Default")
      (node (ref "U18") (pin "2") (pinfunction "GND_2") (pintype "power_in"))
    )
    (net (code "76") (name "unconnected-(U18-RXD-Pad4)") (class "Default")
      (node (ref "U18") (pin "4") (pinfunction "RXD_4") (pintype "output"))
    )
    (net (code "77") (name "unconnected-(U18-S-Pad8)") (class "Default")
      (node (ref "U18") (pin "8") (pinfunction "S_8") (pintype "input"))
    )
    (net (code "78") (name "unconnected-(U18-TXD-Pad1)") (class "Default")
      (node (ref "U18") (pin "1") (pinfunction "TXD_1") (pintype "input"))
    )
    (net (code "79") (name "unconnected-(U18-VCC-Pad3)") (class "Default")
      (node (ref "U18") (pin "3") (pinfunction "VCC_3") (pintype "power_in"))
    )
    (net (code "80") (name "unconnected-(U18-VREF-Pad5)") (class "Default")
      (node (ref "U18") (pin "5") (pinfunction "VREF_5") (pintype "output"))
    )
    (net (code "81") (name "unconnected-(U19-GPIO.2{slash}RS485-Pad12)") (class "Default")
      (node (ref "U19") (pin "12") (pinfunction "GPIO.2/RS485_12") (pintype "bidirectional+no_connect"))
    )
    (net (code "82") (name "unconnected-(U19-GPIO.3{slash}WAKEUP-Pad11)") (class "Default")
      (node (ref "U19") (pin "11") (pinfunction "GPIO.3/WAKEUP_11") (pintype "bidirectional+no_connect"))
    )
    (net (code "83") (name "unconnected-(U19-SUSPEND-Pad17)") (class "Default")
      (node (ref "U19") (pin "17") (pinfunction "SUSPEND_17") (pintype "output"))
    )
    (net (code "84") (name "unconnected-(U19-~{CTS}-Pad18)") (class "Default")
      (node (ref "U19") (pin "18") (pinfunction "~{CTS}_18") (pintype "input+no_connect"))
    )
    (net (code "85") (name "unconnected-(U19-~{DCD}-Pad24)") (class "Default")
      (node (ref "U19") (pin "24") (pinfunction "~{DCD}_24") (pintype "input+no_connect"))
    )
    (net (code "86") (name "unconnected-(U19-~{DSR}-Pad22)") (class "Default")
      (node (ref "U19") (pin "22") (pinfunction "~{DSR}_22") (pintype "input+no_connect"))
    )
    (net (code "87") (name "unconnected-(U19-~{DTR}-Pad23)") (class "Default")
      (node (ref "U19") (pin "23") (pinfunction "~{DTR}_23") (pintype "output+no_connect"))
    )
    (net (code "88") (name "unconnected-(U19-~{RI}{slash}CLK-Pad1)") (class "Default")
      (node (ref "U19") (pin "1") (pinfunction "~{RI}/CLK_1") (pintype "bidirectional+no_connect"))
    )
    (net (code "89") (name "unconnected-(U19-~{RTS}-Pad19)") (class "Default")
      (node (ref "U19") (pin "19") (pinfunction "~{RTS}_19") (pintype "output+no_connect"))
    )
  )
)
